# Power.net
KiCad netlist of a schematic drawn in Altium Designer
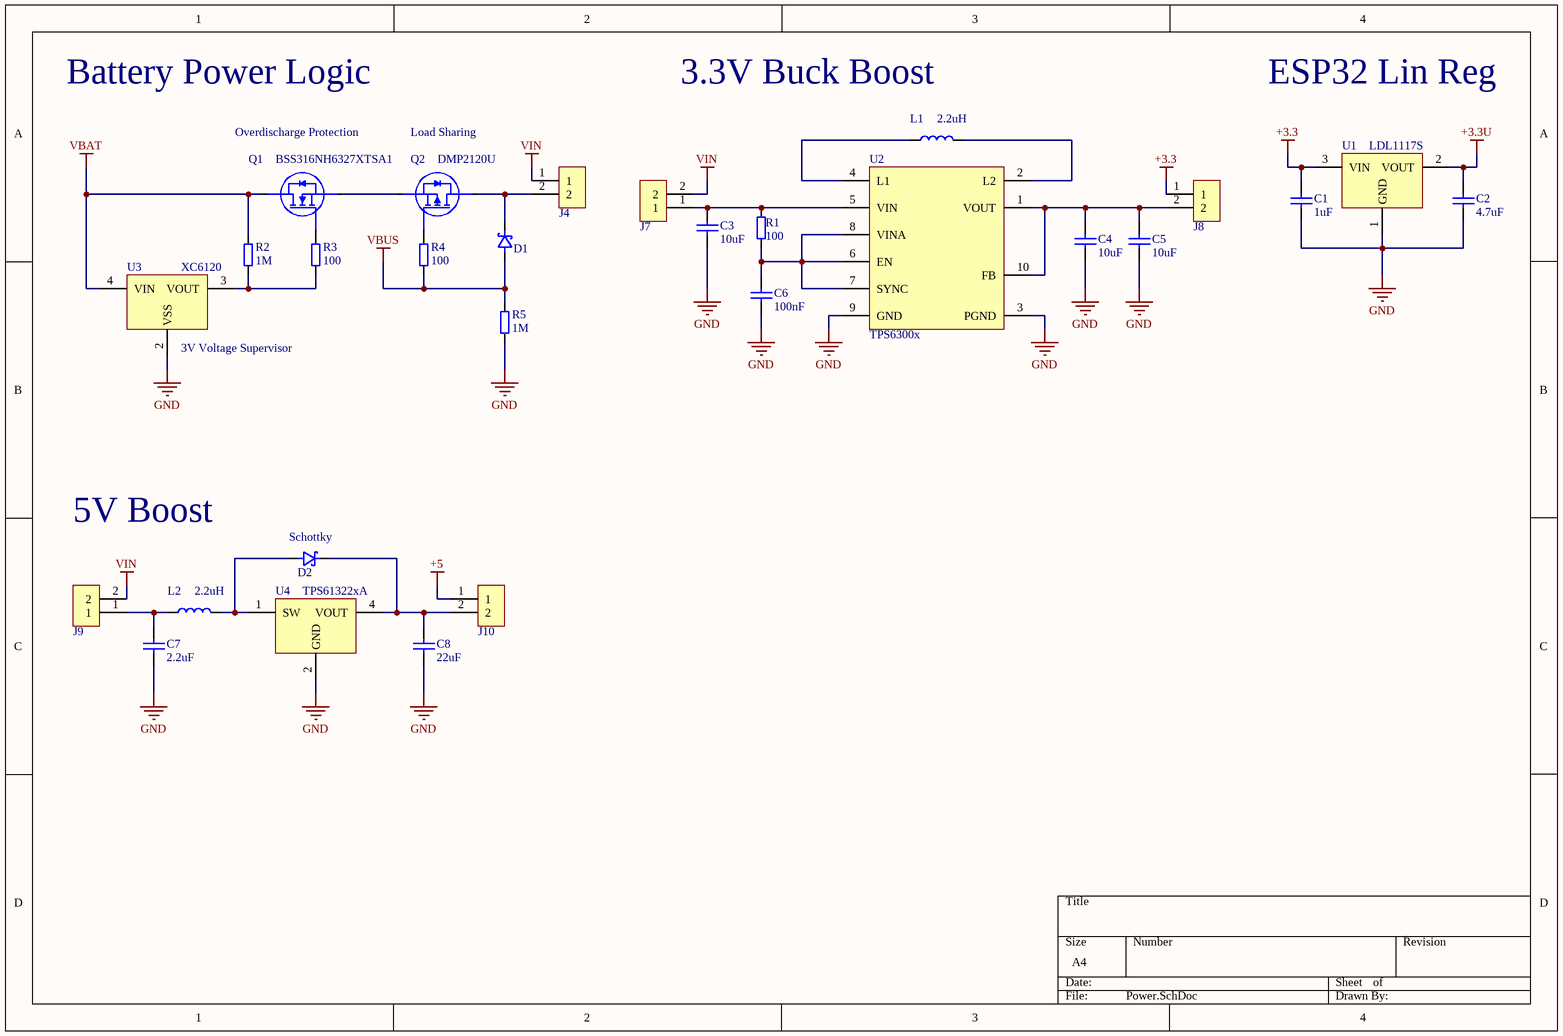
[diagram p0: Power.SchDoc]

(export (version "E")
  (design (tool "Eeschema 10.0.6"))
  (components
    (comp (ref "C1")
      (value "Capacitor_1uF")
      (footprint "CAP 0805")
      (fields (field (name "CAPACITANCE") "1uF"))
      (libsource (lib "BasicComponents") (part "Capacitor_1uF"))
    )
    (comp (ref "C2")
      (value "Capacitor_4.7uF")
      (footprint "CAP 0805")
      (fields (field (name "CAPACITANCE") "4.7uF"))
      (libsource (lib "BasicComponents") (part "Capacitor_4.7uF"))
    )
    (comp (ref "C3")
      (value "Capacitor_10uF")
      (footprint "CAP 0805")
      (fields (field (name "CAPACITANCE") "10uF"))
      (libsource (lib "BasicComponents") (part "Capacitor_10uF"))
    )
    (comp (ref "C4")
      (value "Capacitor_10uF")
      (footprint "CAP 0805")
      (fields (field (name "CAPACITANCE") "10uF"))
      (libsource (lib "BasicComponents") (part "Capacitor_10uF"))
    )
    (comp (ref "C5")
      (value "Capacitor_10uF")
      (footprint "CAP 0805")
      (fields (field (name "CAPACITANCE") "10uF"))
      (libsource (lib "BasicComponents") (part "Capacitor_10uF"))
    )
    (comp (ref "C6")
      (value "Capacitor_100nF")
      (footprint "CAP 0805")
      (fields (field (name "CAPACITANCE") "100nF"))
      (libsource (lib "BasicComponents") (part "Capacitor_100nF"))
    )
    (comp (ref "C7")
      (value "Capacitor_2.2uF")
      (footprint "CAP 0805")
      (fields (field (name "CAPACITANCE") "2.2uF"))
      (libsource (lib "BasicComponents") (part "Capacitor_2.2uF"))
    )
    (comp (ref "C8")
      (value "Capacitor_22uF")
      (footprint "CAP 0805")
      (fields (field (name "CAPACITANCE") "22uF"))
      (libsource (lib "BasicComponents") (part "Capacitor_22uF"))
    )
    (comp (ref "D1")
      (value "Diode_Schottky")
      (footprint "DIOM4226X24N")
      (libsource (lib "BasicComponents") (part "Diode_Schottky"))
    )
    (comp (ref "D2")
      (value "Diode_Schottky")
      (footprint "DIOM4226X24N")
      (libsource (lib "BasicComponents") (part "Diode_Schottky"))
    )
    (comp (ref "J4")
      (value "1x2 Header")
      (footprint "1x2Header")
      (libsource (lib "BasicConnectors") (part "1x2_Header"))
    )
    (comp (ref "J7") (value "1x2 Header") (footprint "1x2Header") (libsource (lib "") (part "1x2_Header_1")))
    (comp (ref "J8")
      (value "1x2 Header")
      (footprint "1x2Header")
      (libsource (lib "BasicConnectors") (part "1x2_Header"))
    )
    (comp (ref "J9") (value "1x2 Header") (footprint "1x2Header") (libsource (lib "") (part "1x2_Header_1")))
    (comp (ref "J10")
      (value "1x2 Header")
      (footprint "1x2Header")
      (libsource (lib "BasicConnectors") (part "1x2_Header"))
    )
    (comp (ref "L1")
      (value "Inductor_2.2uH")
      (footprint "INDP7575X45N")
      (fields (field (name "INDUCTANCE") "2.2uH"))
      (libsource (lib "BasicComponents") (part "Inductor_2.2uH"))
    )
    (comp (ref "L2")
      (value "Inductor_2.2uH")
      (footprint "INDP7575X45N")
      (fields (field (name "INDUCTANCE") "2.2uH"))
      (libsource (lib "BasicComponents") (part "Inductor_2.2uH"))
    )
    (comp (ref "Q1")
      (value "BSS316NH6327XTSA1")
      (footprint "SOT95P245X110-3N")
      (description "N-Channel MOSFET")
      (libsource (lib "CustomModule") (part "BSS316NH6327XTSA1"))
    )
    (comp (ref "Q2")
      (value "DMP2120U")
      (footprint "SOT95P245X110-3N")
      (description "P-Channel MOSFET")
      (libsource (lib "CustomModule") (part "DMP2120U"))
    )
    (comp (ref "R1")
      (value "Resistor_100")
      (footprint "RES 0805")
      (fields (field (name "RESISTANCE") "100"))
      (libsource (lib "") (part "Resistor_100_1"))
    )
    (comp (ref "R2")
      (value "Resistor_1M")
      (footprint "RES 0805")
      (fields (field (name "RESISTANCE") "1M"))
      (libsource (lib "BasicComponents") (part "Resistor_1M"))
    )
    (comp (ref "R3")
      (value "Resistor_100")
      (footprint "RES 0805")
      (fields (field (name "RESISTANCE") "100"))
      (libsource (lib "BasicComponents") (part "Resistor_100"))
    )
    (comp (ref "R4")
      (value "Resistor_100")
      (footprint "RES 0805")
      (fields (field (name "RESISTANCE") "100"))
      (libsource (lib "BasicComponents") (part "Resistor_100"))
    )
    (comp (ref "R5")
      (value "Resistor_1M")
      (footprint "RES 0805")
      (fields (field (name "RESISTANCE") "1M"))
      (libsource (lib "BasicComponents") (part "Resistor_1M"))
    )
    (comp (ref "U1")
      (value "LDL1117S")
      (footprint "SOT223 (Custom)")
      (description "LDO Linear Regulator")
      (libsource (lib "CustomModule") (part "LDL1117S"))
    )
    (comp (ref "U2")
      (value "TPS6300x")
      (footprint "QFN50P300X300X100_HS-11N")
      (description "Buck-Boost Converter")
      (libsource (lib "CustomModule") (part "TPS6300x"))
    )
    (comp (ref "U3")
      (value "XC6120")
      (footprint "TSOP130P210X100-4N")
      (description "Voltage Supervisor")
      (libsource (lib "CustomModule") (part "XC6120"))
    )
    (comp (ref "U4")
      (value "TPS61322xA")
      (footprint "SOT95P280X145-5N")
      (description "Boost Converter")
      (libsource (lib "CustomModule") (part "TPS61322xA"))
    )
  )
  (nets
    (net (code "1") (name "+3.3") (class "Default")
      (node (ref "C1") (pin "2") (pintype "passive"))
      (node (ref "J8") (pin "1") (pinfunction "1_1") (pintype "passive"))
      (node (ref "U1") (pin "3") (pinfunction "VIN_3") (pintype "passive"))
    )
    (net (code "2") (name "+3.3U") (class "Default")
      (node (ref "C2") (pin "2") (pintype "passive"))
      (node (ref "U1") (pin "2") (pinfunction "VOUT_2") (pintype "passive"))
    )
    (net (code "3") (name "+5") (class "Default")
      (node (ref "J10") (pin "1") (pinfunction "1_1") (pintype "passive"))
    )
    (net (code "4") (name "GND") (class "Default")
      (node (ref "C1") (pin "1") (pintype "passive"))
      (node (ref "C2") (pin "1") (pintype "passive"))
      (node (ref "C3") (pin "1") (pintype "passive"))
      (node (ref "C4") (pin "1") (pintype "passive"))
      (node (ref "C5") (pin "1") (pintype "passive"))
      (node (ref "C6") (pin "1") (pintype "passive"))
      (node (ref "C7") (pin "1") (pintype "passive"))
      (node (ref "C8") (pin "1") (pintype "passive"))
      (node (ref "R5") (pin "2") (pintype "passive"))
      (node (ref "U1") (pin "1") (pinfunction "GND_1") (pintype "passive"))
      (node (ref "U2") (pin "3") (pinfunction "PGND_3") (pintype "passive"))
      (node (ref "U2") (pin "9") (pinfunction "GND_9") (pintype "passive"))
      (node (ref "U3") (pin "2") (pinfunction "VSS_2") (pintype "passive"))
      (node (ref "U4") (pin "2") (pinfunction "GND_2") (pintype "passive"))
    )
    (net (code "5") (name "Net-(C7-Pad2)") (class "Default")
      (node (ref "C7") (pin "2") (pintype "passive"))
      (node (ref "J9") (pin "1") (pinfunction "1_1") (pintype "passive"))
      (node (ref "L2") (pin "1") (pintype "passive"))
    )
    (net (code "6") (name "Net-(D1-Pad2)") (class "Default")
      (node (ref "D1") (pin "2") (pintype "passive"))
      (node (ref "J4") (pin "2") (pinfunction "2_2") (pintype "passive"))
      (node (ref "Q2") (pin "3") (pintype "passive"))
    )
    (net (code "7") (name "Net-(Q1-Pad1)") (class "Default")
      (node (ref "Q1") (pin "1") (pintype "passive"))
      (node (ref "R3") (pin "1") (pintype "passive"))
    )
    (net (code "8") (name "Net-(Q1-Pad2)") (class "Default")
      (node (ref "Q1") (pin "2") (pintype "passive"))
      (node (ref "Q2") (pin "2") (pintype "passive"))
    )
    (net (code "9") (name "Net-(Q2-Pad1)") (class "Default")
      (node (ref "Q2") (pin "1") (pintype "passive"))
      (node (ref "R4") (pin "1") (pintype "passive"))
    )
    (net (code "10") (name "Net-(U2-EN)") (class "Default")
      (node (ref "C6") (pin "2") (pintype "passive"))
      (node (ref "R1") (pin "1") (pintype "passive"))
      (node (ref "U2") (pin "6") (pinfunction "EN_6") (pintype "passive"))
      (node (ref "U2") (pin "7") (pinfunction "SYNC_7") (pintype "passive"))
      (node (ref "U2") (pin "8") (pinfunction "VINA_8") (pintype "passive"))
    )
    (net (code "11") (name "Net-(U2-FB)") (class "Default")
      (node (ref "C4") (pin "2") (pintype "passive"))
      (node (ref "C5") (pin "2") (pintype "passive"))
      (node (ref "J8") (pin "2") (pinfunction "2_2") (pintype "passive"))
      (node (ref "U2") (pin "1") (pinfunction "VOUT_1") (pintype "passive"))
      (node (ref "U2") (pin "10") (pinfunction "FB_10") (pintype "passive"))
    )
    (net (code "12") (name "Net-(U2-L1)") (class "Default")
      (node (ref "L1") (pin "1") (pintype "passive"))
      (node (ref "U2") (pin "4") (pinfunction "L1_4") (pintype "passive"))
    )
    (net (code "13") (name "Net-(U2-L2)") (class "Default")
      (node (ref "L1") (pin "2") (pintype "passive"))
      (node (ref "U2") (pin "2") (pinfunction "L2_2") (pintype "passive"))
    )
    (net (code "14") (name "Net-(U2-VIN)") (class "Default")
      (node (ref "C3") (pin "2") (pintype "passive"))
      (node (ref "J7") (pin "1") (pinfunction "1_1") (pintype "passive"))
      (node (ref "R1") (pin "2") (pintype "passive"))
      (node (ref "U2") (pin "5") (pinfunction "VIN_5") (pintype "passive"))
    )
    (net (code "15") (name "Net-(U3-VOUT)") (class "Default")
      (node (ref "R2") (pin "2") (pintype "passive"))
      (node (ref "R3") (pin "2") (pintype "passive"))
      (node (ref "U3") (pin "3") (pinfunction "VOUT_3") (pintype "passive"))
    )
    (net (code "16") (name "Net-(U4-SW)") (class "Default")
      (node (ref "D2") (pin "1") (pintype "passive"))
      (node (ref "L2") (pin "2") (pintype "passive"))
      (node (ref "U4") (pin "1") (pinfunction "SW_1") (pintype "passive"))
    )
    (net (code "17") (name "Net-(U4-VOUT)") (class "Default")
      (node (ref "C8") (pin "2") (pintype "passive"))
      (node (ref "D2") (pin "2") (pintype "passive"))
      (node (ref "J10") (pin "2") (pinfunction "2_2") (pintype "passive"))
      (node (ref "U4") (pin "4") (pinfunction "VOUT_4") (pintype "passive"))
    )
    (net (code "18") (name "VBAT") (class "Default")
      (node (ref "Q1") (pin "3") (pintype "passive"))
      (node (ref "R2") (pin "1") (pintype "passive"))
      (node (ref "U3") (pin "4") (pinfunction "VIN_4") (pintype "passive"))
    )
    (net (code "19") (name "VBUS") (class "Default")
      (node (ref "D1") (pin "1") (pintype "passive"))
      (node (ref "R4") (pin "2") (pintype "passive"))
      (node (ref "R5") (pin "1") (pintype "passive"))
    )
    (net (code "20") (name "VIN") (class "Default")
      (node (ref "J4") (pin "1") (pinfunction "1_1") (pintype "passive"))
      (node (ref "J7") (pin "2") (pinfunction "2_2") (pintype "passive"))
      (node (ref "J9") (pin "2") (pinfunction "2_2") (pintype "passive"))
    )
  )
)
